# Summing.net
KiCad netlist of a schematic drawn in EAGLE
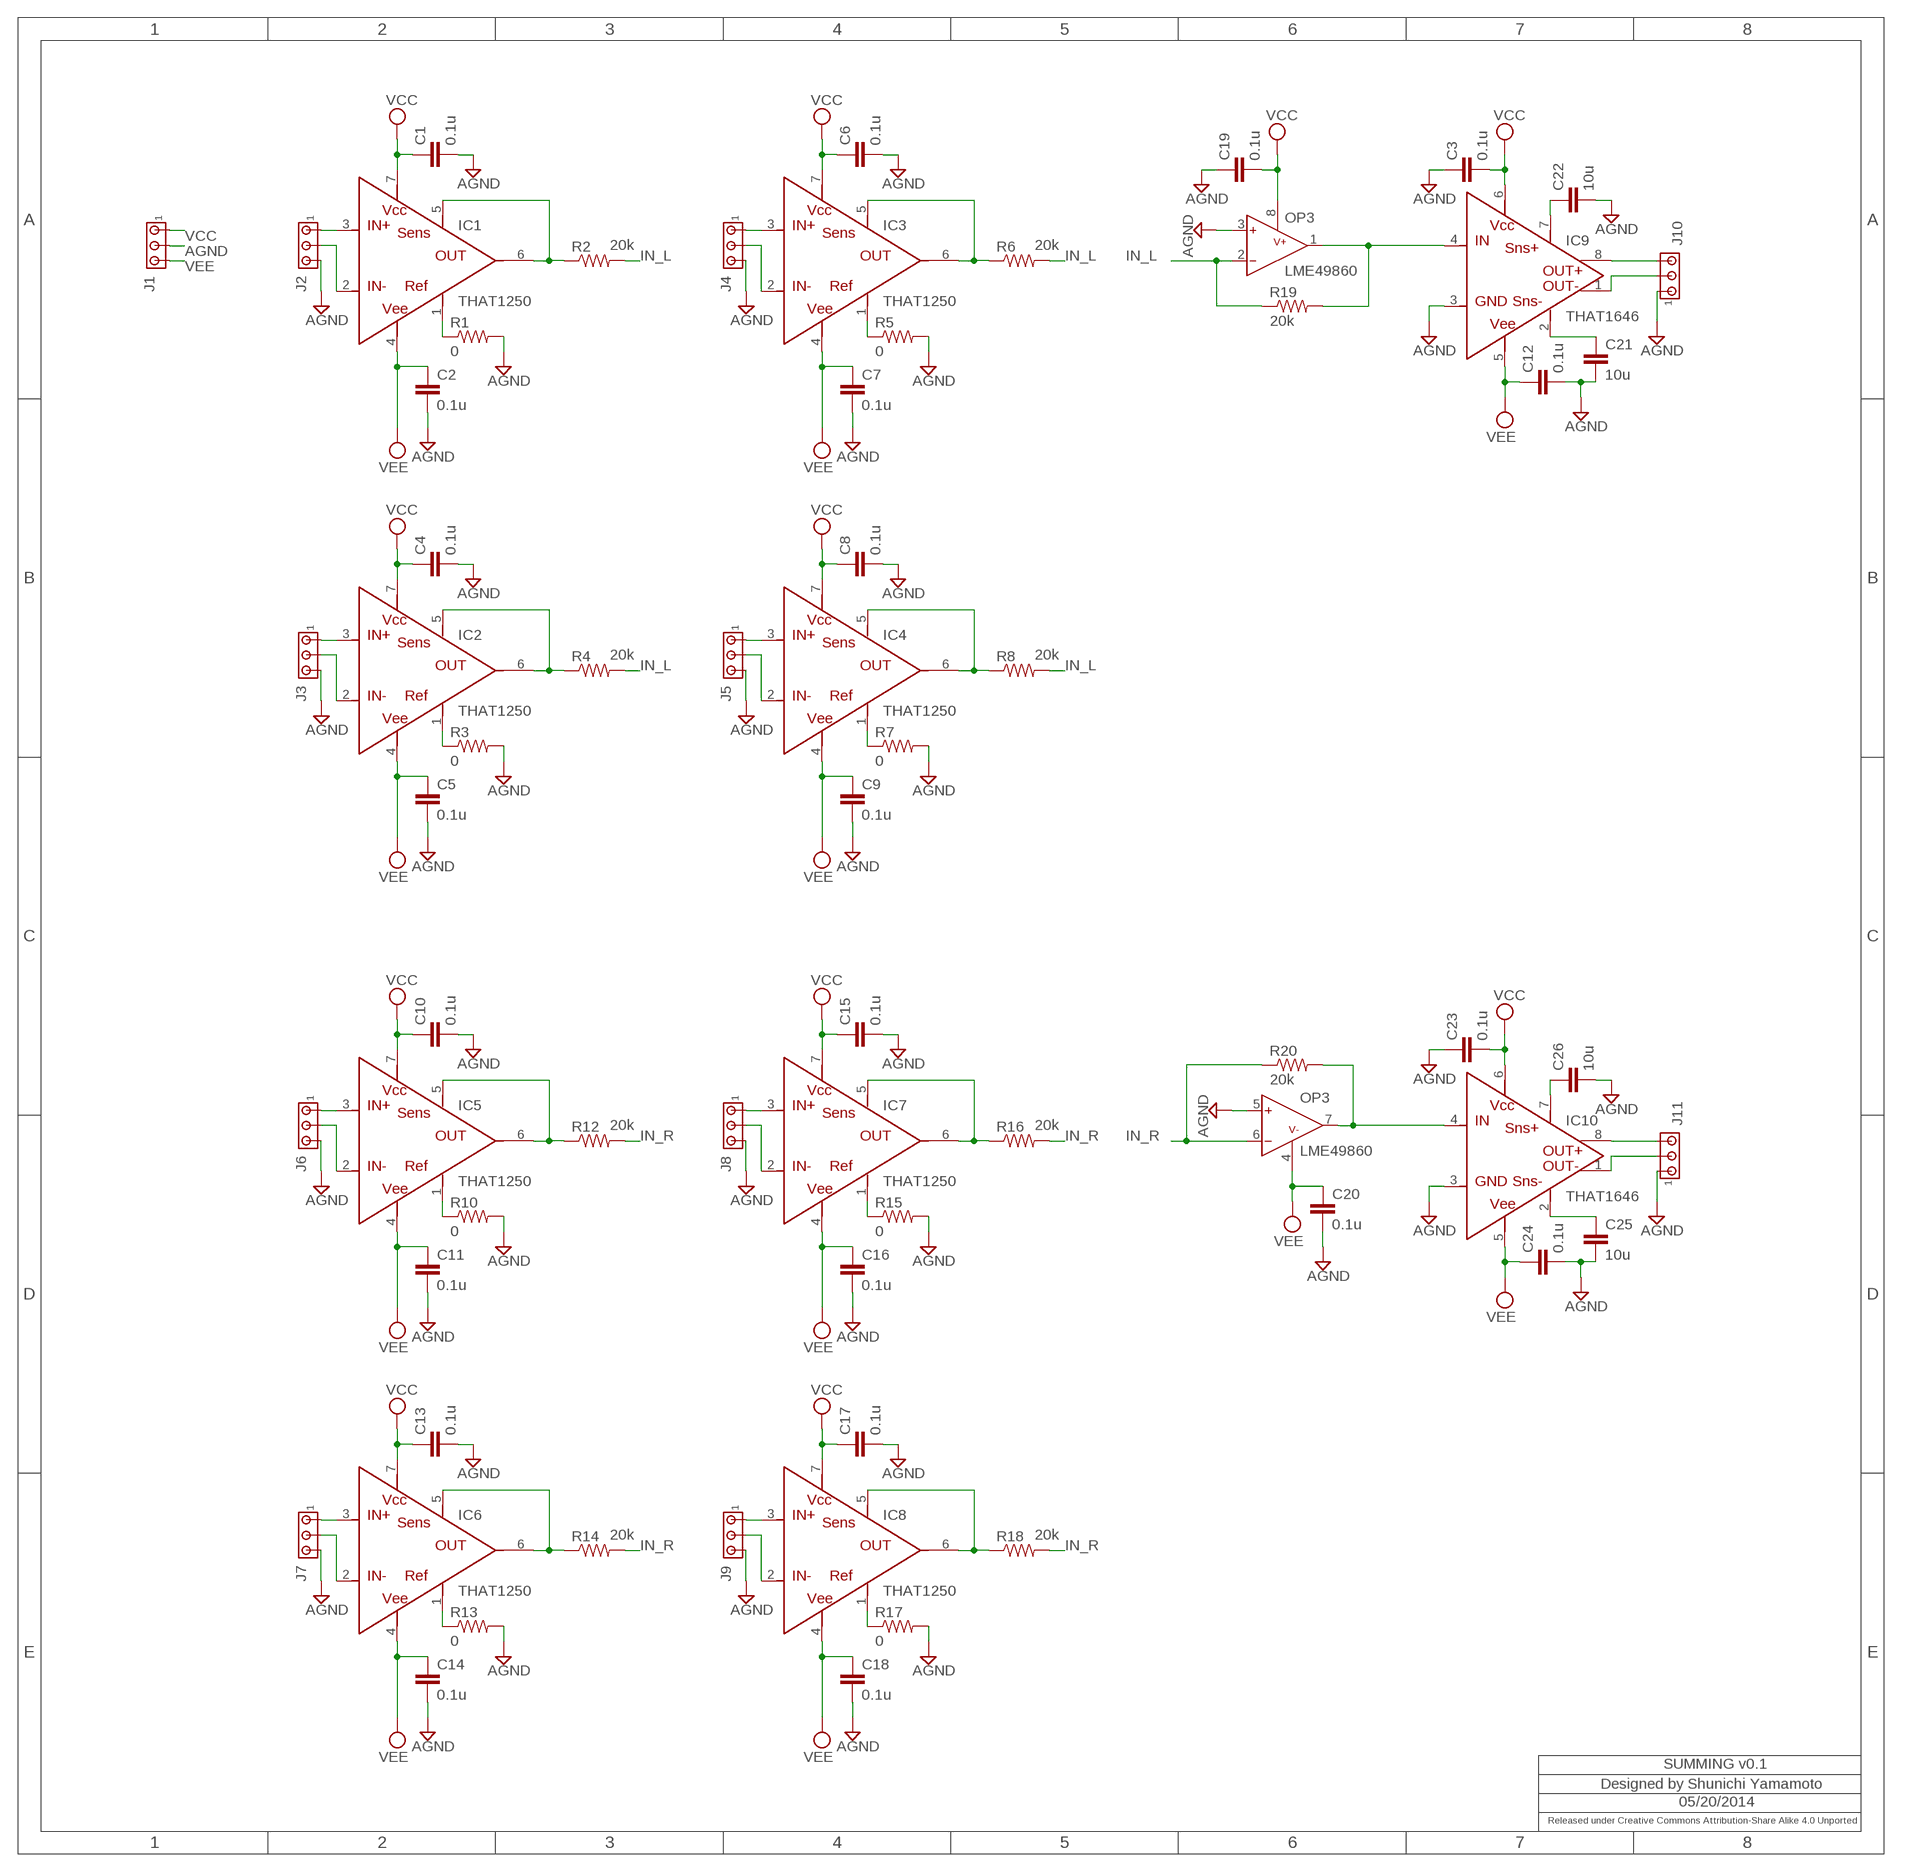
[diagram p0: schematic, sheet 1]

(export (version "E")
  (design (tool "Eeschema 10.0.6"))
  (components
    (comp (ref "C1")
      (value "0.1u")
      (footprint "eagle-import:C2012")
      (libsource (lib "eagle-import") (part "C-EUC2012"))
    )
    (comp (ref "C2")
      (value "0.1u")
      (footprint "eagle-import:C2012")
      (libsource (lib "eagle-import") (part "C-EUC2012"))
    )
    (comp (ref "C3")
      (value "0.1u")
      (footprint "eagle-import:C2012")
      (libsource (lib "eagle-import") (part "C-EUC2012"))
    )
    (comp (ref "C4")
      (value "0.1u")
      (footprint "eagle-import:C2012")
      (libsource (lib "eagle-import") (part "C-EUC2012"))
    )
    (comp (ref "C5")
      (value "0.1u")
      (footprint "eagle-import:C2012")
      (libsource (lib "eagle-import") (part "C-EUC2012"))
    )
    (comp (ref "C6")
      (value "0.1u")
      (footprint "eagle-import:C2012")
      (libsource (lib "eagle-import") (part "C-EUC2012"))
    )
    (comp (ref "C7")
      (value "0.1u")
      (footprint "eagle-import:C2012")
      (libsource (lib "eagle-import") (part "C-EUC2012"))
    )
    (comp (ref "C8")
      (value "0.1u")
      (footprint "eagle-import:C2012")
      (libsource (lib "eagle-import") (part "C-EUC2012"))
    )
    (comp (ref "C9")
      (value "0.1u")
      (footprint "eagle-import:C2012")
      (libsource (lib "eagle-import") (part "C-EUC2012"))
    )
    (comp (ref "C10")
      (value "0.1u")
      (footprint "eagle-import:C2012")
      (libsource (lib "eagle-import") (part "C-EUC2012"))
    )
    (comp (ref "C11")
      (value "0.1u")
      (footprint "eagle-import:C2012")
      (libsource (lib "eagle-import") (part "C-EUC2012"))
    )
    (comp (ref "C12")
      (value "0.1u")
      (footprint "eagle-import:C2012")
      (libsource (lib "eagle-import") (part "C-EUC2012"))
    )
    (comp (ref "C13")
      (value "0.1u")
      (footprint "eagle-import:C2012")
      (libsource (lib "eagle-import") (part "C-EUC2012"))
    )
    (comp (ref "C14")
      (value "0.1u")
      (footprint "eagle-import:C2012")
      (libsource (lib "eagle-import") (part "C-EUC2012"))
    )
    (comp (ref "C15")
      (value "0.1u")
      (footprint "eagle-import:C2012")
      (libsource (lib "eagle-import") (part "C-EUC2012"))
    )
    (comp (ref "C16")
      (value "0.1u")
      (footprint "eagle-import:C2012")
      (libsource (lib "eagle-import") (part "C-EUC2012"))
    )
    (comp (ref "C17")
      (value "0.1u")
      (footprint "eagle-import:C2012")
      (libsource (lib "eagle-import") (part "C-EUC2012"))
    )
    (comp (ref "C18")
      (value "0.1u")
      (footprint "eagle-import:C2012")
      (libsource (lib "eagle-import") (part "C-EUC2012"))
    )
    (comp (ref "C19")
      (value "0.1u")
      (footprint "eagle-import:C2012")
      (libsource (lib "eagle-import") (part "C-EUC2012"))
    )
    (comp (ref "C20")
      (value "0.1u")
      (footprint "eagle-import:C2012")
      (libsource (lib "eagle-import") (part "C-EUC2012"))
    )
    (comp (ref "C21")
      (value "10u")
      (footprint "eagle-import:C2012")
      (libsource (lib "eagle-import") (part "C-EUC2012"))
    )
    (comp (ref "C22")
      (value "10u")
      (footprint "eagle-import:C2012")
      (libsource (lib "eagle-import") (part "C-EUC2012"))
    )
    (comp (ref "C23")
      (value "0.1u")
      (footprint "eagle-import:C2012")
      (libsource (lib "eagle-import") (part "C-EUC2012"))
    )
    (comp (ref "C24")
      (value "0.1u")
      (footprint "eagle-import:C2012")
      (libsource (lib "eagle-import") (part "C-EUC2012"))
    )
    (comp (ref "C25")
      (value "10u")
      (footprint "eagle-import:C2012")
      (libsource (lib "eagle-import") (part "C-EUC2012"))
    )
    (comp (ref "C26")
      (value "10u")
      (footprint "eagle-import:C2012")
      (libsource (lib "eagle-import") (part "C-EUC2012"))
    )
    (comp (ref "IC1")
      (value "THAT1250")
      (footprint "eagle-import:SOIC8@1")
      (libsource (lib "eagle-import") (part "THAT1250"))
    )
    (comp (ref "IC2")
      (value "THAT1250")
      (footprint "eagle-import:SOIC8@1")
      (libsource (lib "eagle-import") (part "THAT1250"))
    )
    (comp (ref "IC3")
      (value "THAT1250")
      (footprint "eagle-import:SOIC8@1")
      (libsource (lib "eagle-import") (part "THAT1250"))
    )
    (comp (ref "IC4")
      (value "THAT1250")
      (footprint "eagle-import:SOIC8@1")
      (libsource (lib "eagle-import") (part "THAT1250"))
    )
    (comp (ref "IC5")
      (value "THAT1250")
      (footprint "eagle-import:SOIC8@1")
      (libsource (lib "eagle-import") (part "THAT1250"))
    )
    (comp (ref "IC6")
      (value "THAT1250")
      (footprint "eagle-import:SOIC8@1")
      (libsource (lib "eagle-import") (part "THAT1250"))
    )
    (comp (ref "IC7")
      (value "THAT1250")
      (footprint "eagle-import:SOIC8@1")
      (libsource (lib "eagle-import") (part "THAT1250"))
    )
    (comp (ref "IC8")
      (value "THAT1250")
      (footprint "eagle-import:SOIC8@1")
      (libsource (lib "eagle-import") (part "THAT1250"))
    )
    (comp (ref "IC9")
      (value "THAT1646")
      (footprint "eagle-import:SOIC8")
      (libsource (lib "eagle-import") (part "THAT1646"))
    )
    (comp (ref "IC10")
      (value "THAT1646")
      (footprint "eagle-import:SOIC8")
      (libsource (lib "eagle-import") (part "THAT1646"))
    )
    (comp (ref "J1")
      (value "MTA03-156")
      (footprint "eagle-import:1X3MTA")
      (libsource (lib "eagle-import") (part "MTA03-156"))
    )
    (comp (ref "J2")
      (value "MTA03-100")
      (footprint "eagle-import:10X03MTA")
      (libsource (lib "eagle-import") (part "MTA03-100"))
    )
    (comp (ref "J3")
      (value "MTA03-100")
      (footprint "eagle-import:10X03MTA")
      (libsource (lib "eagle-import") (part "MTA03-100"))
    )
    (comp (ref "J4")
      (value "MTA03-100")
      (footprint "eagle-import:10X03MTA")
      (libsource (lib "eagle-import") (part "MTA03-100"))
    )
    (comp (ref "J5")
      (value "MTA03-100")
      (footprint "eagle-import:10X03MTA")
      (libsource (lib "eagle-import") (part "MTA03-100"))
    )
    (comp (ref "J6")
      (value "MTA03-100")
      (footprint "eagle-import:10X03MTA")
      (libsource (lib "eagle-import") (part "MTA03-100"))
    )
    (comp (ref "J7")
      (value "MTA03-100")
      (footprint "eagle-import:10X03MTA")
      (libsource (lib "eagle-import") (part "MTA03-100"))
    )
    (comp (ref "J8")
      (value "MTA03-100")
      (footprint "eagle-import:10X03MTA")
      (libsource (lib "eagle-import") (part "MTA03-100"))
    )
    (comp (ref "J9")
      (value "MTA03-100")
      (footprint "eagle-import:10X03MTA")
      (libsource (lib "eagle-import") (part "MTA03-100"))
    )
    (comp (ref "J10")
      (value "MTA03-100")
      (footprint "eagle-import:10X03MTA")
      (libsource (lib "eagle-import") (part "MTA03-100"))
    )
    (comp (ref "J11")
      (value "MTA03-100")
      (footprint "eagle-import:10X03MTA")
      (libsource (lib "eagle-import") (part "MTA03-100"))
    )
    (comp (ref "OP3")
      (value "LME49860")
      (footprint "eagle-import:SOIC8@2")
      (libsource (lib "eagle-import") (part "LME49860"))
    )
    (comp (ref "R1")
      (value "0")
      (footprint "eagle-import:0805")
      (libsource (lib "eagle-import") (part "RESISTOR0805-RES"))
    )
    (comp (ref "R2")
      (value "20k")
      (footprint "eagle-import:0805")
      (libsource (lib "eagle-import") (part "RESISTOR0805-RES"))
    )
    (comp (ref "R3")
      (value "0")
      (footprint "eagle-import:0805")
      (libsource (lib "eagle-import") (part "RESISTOR0805-RES"))
    )
    (comp (ref "R4")
      (value "20k")
      (footprint "eagle-import:0805")
      (libsource (lib "eagle-import") (part "RESISTOR0805-RES"))
    )
    (comp (ref "R5")
      (value "0")
      (footprint "eagle-import:0805")
      (libsource (lib "eagle-import") (part "RESISTOR0805-RES"))
    )
    (comp (ref "R6")
      (value "20k")
      (footprint "eagle-import:0805")
      (libsource (lib "eagle-import") (part "RESISTOR0805-RES"))
    )
    (comp (ref "R7")
      (value "0")
      (footprint "eagle-import:0805")
      (libsource (lib "eagle-import") (part "RESISTOR0805-RES"))
    )
    (comp (ref "R8")
      (value "20k")
      (footprint "eagle-import:0805")
      (libsource (lib "eagle-import") (part "RESISTOR0805-RES"))
    )
    (comp (ref "R10")
      (value "0")
      (footprint "eagle-import:0805")
      (libsource (lib "eagle-import") (part "RESISTOR0805-RES"))
    )
    (comp (ref "R12")
      (value "20k")
      (footprint "eagle-import:0805")
      (libsource (lib "eagle-import") (part "RESISTOR0805-RES"))
    )
    (comp (ref "R13")
      (value "0")
      (footprint "eagle-import:0805")
      (libsource (lib "eagle-import") (part "RESISTOR0805-RES"))
    )
    (comp (ref "R14")
      (value "20k")
      (footprint "eagle-import:0805")
      (libsource (lib "eagle-import") (part "RESISTOR0805-RES"))
    )
    (comp (ref "R15")
      (value "0")
      (footprint "eagle-import:0805")
      (libsource (lib "eagle-import") (part "RESISTOR0805-RES"))
    )
    (comp (ref "R16")
      (value "20k")
      (footprint "eagle-import:0805")
      (libsource (lib "eagle-import") (part "RESISTOR0805-RES"))
    )
    (comp (ref "R17")
      (value "0")
      (footprint "eagle-import:0805")
      (libsource (lib "eagle-import") (part "RESISTOR0805-RES"))
    )
    (comp (ref "R18")
      (value "20k")
      (footprint "eagle-import:0805")
      (libsource (lib "eagle-import") (part "RESISTOR0805-RES"))
    )
    (comp (ref "R19")
      (value "20k")
      (footprint "eagle-import:0805")
      (libsource (lib "eagle-import") (part "RESISTOR0805-RES"))
    )
    (comp (ref "R20")
      (value "20k")
      (footprint "eagle-import:0805")
      (libsource (lib "eagle-import") (part "RESISTOR0805-RES"))
    )
  )
  (nets
    (net (code "1") (name "/IN_L") (class "Default")
      (node (ref "OP3") (pin "2") (pinfunction "INA-_2") (pintype "input"))
      (node (ref "R19") (pin "1") (pinfunction "1_1") (pintype "passive"))
      (node (ref "R2") (pin "2") (pinfunction "2_2") (pintype "passive"))
      (node (ref "R4") (pin "2") (pinfunction "2_2") (pintype "passive"))
      (node (ref "R6") (pin "2") (pinfunction "2_2") (pintype "passive"))
      (node (ref "R8") (pin "2") (pinfunction "2_2") (pintype "passive"))
    )
    (net (code "2") (name "/IN_R") (class "Default")
      (node (ref "OP3") (pin "6") (pinfunction "INB-_6") (pintype "input"))
      (node (ref "R12") (pin "2") (pinfunction "2_2") (pintype "passive"))
      (node (ref "R14") (pin "2") (pinfunction "2_2") (pintype "passive"))
      (node (ref "R16") (pin "2") (pinfunction "2_2") (pintype "passive"))
      (node (ref "R18") (pin "2") (pinfunction "2_2") (pintype "passive"))
      (node (ref "R20") (pin "1") (pinfunction "1_1") (pintype "passive"))
    )
    (net (code "3") (name "AGND") (class "Default")
      (node (ref "C1") (pin "2") (pinfunction "2_2") (pintype "passive"))
      (node (ref "C10") (pin "2") (pinfunction "2_2") (pintype "passive"))
      (node (ref "C11") (pin "2") (pinfunction "2_2") (pintype "passive"))
      (node (ref "C12") (pin "2") (pinfunction "2_2") (pintype "passive"))
      (node (ref "C13") (pin "2") (pinfunction "2_2") (pintype "passive"))
      (node (ref "C14") (pin "2") (pinfunction "2_2") (pintype "passive"))
      (node (ref "C15") (pin "2") (pinfunction "2_2") (pintype "passive"))
      (node (ref "C16") (pin "2") (pinfunction "2_2") (pintype "passive"))
      (node (ref "C17") (pin "2") (pinfunction "2_2") (pintype "passive"))
      (node (ref "C18") (pin "2") (pinfunction "2_2") (pintype "passive"))
      (node (ref "C19") (pin "1") (pinfunction "1_1") (pintype "passive"))
      (node (ref "C2") (pin "2") (pinfunction "2_2") (pintype "passive"))
      (node (ref "C20") (pin "2") (pinfunction "2_2") (pintype "passive"))
      (node (ref "C21") (pin "2") (pinfunction "2_2") (pintype "passive"))
      (node (ref "C22") (pin "2") (pinfunction "2_2") (pintype "passive"))
      (node (ref "C23") (pin "1") (pinfunction "1_1") (pintype "passive"))
      (node (ref "C24") (pin "2") (pinfunction "2_2") (pintype "passive"))
      (node (ref "C25") (pin "2") (pinfunction "2_2") (pintype "passive"))
      (node (ref "C26") (pin "2") (pinfunction "2_2") (pintype "passive"))
      (node (ref "C3") (pin "1") (pinfunction "1_1") (pintype "passive"))
      (node (ref "C4") (pin "2") (pinfunction "2_2") (pintype "passive"))
      (node (ref "C5") (pin "2") (pinfunction "2_2") (pintype "passive"))
      (node (ref "C6") (pin "2") (pinfunction "2_2") (pintype "passive"))
      (node (ref "C7") (pin "2") (pinfunction "2_2") (pintype "passive"))
      (node (ref "C8") (pin "2") (pinfunction "2_2") (pintype "passive"))
      (node (ref "C9") (pin "2") (pinfunction "2_2") (pintype "passive"))
      (node (ref "IC10") (pin "3") (pinfunction "GND_3") (pintype "input"))
      (node (ref "IC9") (pin "3") (pinfunction "GND_3") (pintype "input"))
      (node (ref "J1") (pin "2") (pinfunction "2_2") (pintype "passive"))
      (node (ref "J10") (pin "1") (pinfunction "1_1") (pintype "passive"))
      (node (ref "J11") (pin "1") (pinfunction "1_1") (pintype "passive"))
      (node (ref "J2") (pin "3") (pinfunction "3_3") (pintype "passive"))
      (node (ref "J3") (pin "3") (pinfunction "3_3") (pintype "passive"))
      (node (ref "J4") (pin "3") (pinfunction "3_3") (pintype "passive"))
      (node (ref "J5") (pin "3") (pinfunction "3_3") (pintype "passive"))
      (node (ref "J6") (pin "3") (pinfunction "3_3") (pintype "passive"))
      (node (ref "J7") (pin "3") (pinfunction "3_3") (pintype "passive"))
      (node (ref "J8") (pin "3") (pinfunction "3_3") (pintype "passive"))
      (node (ref "J9") (pin "3") (pinfunction "3_3") (pintype "passive"))
      (node (ref "OP3") (pin "3") (pinfunction "INA+_3") (pintype "input"))
      (node (ref "OP3") (pin "5") (pinfunction "INB+_5") (pintype "input"))
      (node (ref "R1") (pin "2") (pinfunction "2_2") (pintype "passive"))
      (node (ref "R10") (pin "2") (pinfunction "2_2") (pintype "passive"))
      (node (ref "R13") (pin "2") (pinfunction "2_2") (pintype "passive"))
      (node (ref "R15") (pin "2") (pinfunction "2_2") (pintype "passive"))
      (node (ref "R17") (pin "2") (pinfunction "2_2") (pintype "passive"))
      (node (ref "R3") (pin "2") (pinfunction "2_2") (pintype "passive"))
      (node (ref "R5") (pin "2") (pinfunction "2_2") (pintype "passive"))
      (node (ref "R7") (pin "2") (pinfunction "2_2") (pintype "passive"))
    )
    (net (code "4") (name "Net-(IC1-IN+)") (class "Default")
      (node (ref "IC1") (pin "3") (pinfunction "IN+_3") (pintype "input"))
      (node (ref "J2") (pin "1") (pinfunction "1_1") (pintype "passive"))
    )
    (net (code "5") (name "Net-(IC1-IN-)") (class "Default")
      (node (ref "IC1") (pin "2") (pinfunction "IN-_2") (pintype "input"))
      (node (ref "J2") (pin "2") (pinfunction "2_2") (pintype "passive"))
    )
    (net (code "6") (name "Net-(IC1-OUT)") (class "Default")
      (node (ref "IC1") (pin "5") (pinfunction "SENS_5") (pintype "power_in"))
      (node (ref "IC1") (pin "6") (pinfunction "OUT_6") (pintype "output"))
      (node (ref "R2") (pin "1") (pinfunction "1_1") (pintype "passive"))
    )
    (net (code "7") (name "Net-(IC1-REF)") (class "Default")
      (node (ref "IC1") (pin "1") (pinfunction "REF_1") (pintype "input"))
      (node (ref "R1") (pin "1") (pinfunction "1_1") (pintype "passive"))
    )
    (net (code "8") (name "Net-(IC2-IN+)") (class "Default")
      (node (ref "IC2") (pin "3") (pinfunction "IN+_3") (pintype "input"))
      (node (ref "J3") (pin "1") (pinfunction "1_1") (pintype "passive"))
    )
    (net (code "9") (name "Net-(IC2-IN-)") (class "Default")
      (node (ref "IC2") (pin "2") (pinfunction "IN-_2") (pintype "input"))
      (node (ref "J3") (pin "2") (pinfunction "2_2") (pintype "passive"))
    )
    (net (code "10") (name "Net-(IC2-OUT)") (class "Default")
      (node (ref "IC2") (pin "5") (pinfunction "SENS_5") (pintype "power_in"))
      (node (ref "IC2") (pin "6") (pinfunction "OUT_6") (pintype "output"))
      (node (ref "R4") (pin "1") (pinfunction "1_1") (pintype "passive"))
    )
    (net (code "11") (name "Net-(IC2-REF)") (class "Default")
      (node (ref "IC2") (pin "1") (pinfunction "REF_1") (pintype "input"))
      (node (ref "R3") (pin "1") (pinfunction "1_1") (pintype "passive"))
    )
    (net (code "12") (name "Net-(IC3-IN+)") (class "Default")
      (node (ref "IC3") (pin "3") (pinfunction "IN+_3") (pintype "input"))
      (node (ref "J4") (pin "1") (pinfunction "1_1") (pintype "passive"))
    )
    (net (code "13") (name "Net-(IC3-IN-)") (class "Default")
      (node (ref "IC3") (pin "2") (pinfunction "IN-_2") (pintype "input"))
      (node (ref "J4") (pin "2") (pinfunction "2_2") (pintype "passive"))
    )
    (net (code "14") (name "Net-(IC3-OUT)") (class "Default")
      (node (ref "IC3") (pin "5") (pinfunction "SENS_5") (pintype "power_in"))
      (node (ref "IC3") (pin "6") (pinfunction "OUT_6") (pintype "output"))
      (node (ref "R6") (pin "1") (pinfunction "1_1") (pintype "passive"))
    )
    (net (code "15") (name "Net-(IC3-REF)") (class "Default")
      (node (ref "IC3") (pin "1") (pinfunction "REF_1") (pintype "input"))
      (node (ref "R5") (pin "1") (pinfunction "1_1") (pintype "passive"))
    )
    (net (code "16") (name "Net-(IC4-IN+)") (class "Default")
      (node (ref "IC4") (pin "3") (pinfunction "IN+_3") (pintype "input"))
      (node (ref "J5") (pin "1") (pinfunction "1_1") (pintype "passive"))
    )
    (net (code "17") (name "Net-(IC4-IN-)") (class "Default")
      (node (ref "IC4") (pin "2") (pinfunction "IN-_2") (pintype "input"))
      (node (ref "J5") (pin "2") (pinfunction "2_2") (pintype "passive"))
    )
    (net (code "18") (name "Net-(IC4-OUT)") (class "Default")
      (node (ref "IC4") (pin "5") (pinfunction "SENS_5") (pintype "power_in"))
      (node (ref "IC4") (pin "6") (pinfunction "OUT_6") (pintype "output"))
      (node (ref "R8") (pin "1") (pinfunction "1_1") (pintype "passive"))
    )
    (net (code "19") (name "Net-(IC4-REF)") (class "Default")
      (node (ref "IC4") (pin "1") (pinfunction "REF_1") (pintype "input"))
      (node (ref "R7") (pin "1") (pinfunction "1_1") (pintype "passive"))
    )
    (net (code "20") (name "Net-(IC5-IN+)") (class "Default")
      (node (ref "IC5") (pin "3") (pinfunction "IN+_3") (pintype "input"))
      (node (ref "J6") (pin "1") (pinfunction "1_1") (pintype "passive"))
    )
    (net (code "21") (name "Net-(IC5-IN-)") (class "Default")
      (node (ref "IC5") (pin "2") (pinfunction "IN-_2") (pintype "input"))
      (node (ref "J6") (pin "2") (pinfunction "2_2") (pintype "passive"))
    )
    (net (code "22") (name "Net-(IC5-OUT)") (class "Default")
      (node (ref "IC5") (pin "5") (pinfunction "SENS_5") (pintype "power_in"))
      (node (ref "IC5") (pin "6") (pinfunction "OUT_6") (pintype "output"))
      (node (ref "R12") (pin "1") (pinfunction "1_1") (pintype "passive"))
    )
    (net (code "23") (name "Net-(IC5-REF)") (class "Default")
      (node (ref "IC5") (pin "1") (pinfunction "REF_1") (pintype "input"))
      (node (ref "R10") (pin "1") (pinfunction "1_1") (pintype "passive"))
    )
    (net (code "24") (name "Net-(IC6-IN+)") (class "Default")
      (node (ref "IC6") (pin "3") (pinfunction "IN+_3") (pintype "input"))
      (node (ref "J7") (pin "1") (pinfunction "1_1") (pintype "passive"))
    )
    (net (code "25") (name "Net-(IC6-IN-)") (class "Default")
      (node (ref "IC6") (pin "2") (pinfunction "IN-_2") (pintype "input"))
      (node (ref "J7") (pin "2") (pinfunction "2_2") (pintype "passive"))
    )
    (net (code "26") (name "Net-(IC6-OUT)") (class "Default")
      (node (ref "IC6") (pin "5") (pinfunction "SENS_5") (pintype "power_in"))
      (node (ref "IC6") (pin "6") (pinfunction "OUT_6") (pintype "output"))
      (node (ref "R14") (pin "1") (pinfunction "1_1") (pintype "passive"))
    )
    (net (code "27") (name "Net-(IC6-REF)") (class "Default")
      (node (ref "IC6") (pin "1") (pinfunction "REF_1") (pintype "input"))
      (node (ref "R13") (pin "1") (pinfunction "1_1") (pintype "passive"))
    )
    (net (code "28") (name "Net-(IC7-IN+)") (class "Default")
      (node (ref "IC7") (pin "3") (pinfunction "IN+_3") (pintype "input"))
      (node (ref "J8") (pin "1") (pinfunction "1_1") (pintype "passive"))
    )
    (net (code "29") (name "Net-(IC7-IN-)") (class "Default")
      (node (ref "IC7") (pin "2") (pinfunction "IN-_2") (pintype "input"))
      (node (ref "J8") (pin "2") (pinfunction "2_2") (pintype "passive"))
    )
    (net (code "30") (name "Net-(IC7-OUT)") (class "Default")
      (node (ref "IC7") (pin "5") (pinfunction "SENS_5") (pintype "power_in"))
      (node (ref "IC7") (pin "6") (pinfunction "OUT_6") (pintype "output"))
      (node (ref "R16") (pin "1") (pinfunction "1_1") (pintype "passive"))
    )
    (net (code "31") (name "Net-(IC7-REF)") (class "Default")
      (node (ref "IC7") (pin "1") (pinfunction "REF_1") (pintype "input"))
      (node (ref "R15") (pin "1") (pinfunction "1_1") (pintype "passive"))
    )
    (net (code "32") (name "Net-(IC8-IN+)") (class "Default")
      (node (ref "IC8") (pin "3") (pinfunction "IN+_3") (pintype "input"))
      (node (ref "J9") (pin "1") (pinfunction "1_1") (pintype "passive"))
    )
    (net (code "33") (name "Net-(IC8-IN-)") (class "Default")
      (node (ref "IC8") (pin "2") (pinfunction "IN-_2") (pintype "input"))
      (node (ref "J9") (pin "2") (pinfunction "2_2") (pintype "passive"))
    )
    (net (code "34") (name "Net-(IC8-OUT)") (class "Default")
      (node (ref "IC8") (pin "5") (pinfunction "SENS_5") (pintype "power_in"))
      (node (ref "IC8") (pin "6") (pinfunction "OUT_6") (pintype "output"))
      (node (ref "R18") (pin "1") (pinfunction "1_1") (pintype "passive"))
    )
    (net (code "35") (name "Net-(IC8-REF)") (class "Default")
      (node (ref "IC8") (pin "1") (pinfunction "REF_1") (pintype "input"))
      (node (ref "R17") (pin "1") (pinfunction "1_1") (pintype "passive"))
    )
    (net (code "36") (name "Net-(IC9-IN)") (class "Default")
      (node (ref "IC9") (pin "4") (pinfunction "IN_4") (pintype "input"))
      (node (ref "OP3") (pin "1") (pinfunction "OUTA_1") (pintype "output"))
      (node (ref "R19") (pin "2") (pinfunction "2_2") (pintype "passive"))
    )
    (net (code "37") (name "Net-(IC9-OUT+)") (class "Default")
      (node (ref "IC9") (pin "8") (pinfunction "OUT+_8") (pintype "output"))
      (node (ref "J10") (pin "3") (pinfunction "3_3") (pintype "passive"))
    )
    (net (code "38") (name "Net-(IC9-OUT-)") (class "Default")
      (node (ref "IC9") (pin "1") (pinfunction "OUT-_1") (pintype "output"))
      (node (ref "J10") (pin "2") (pinfunction "2_2") (pintype "passive"))
    )
    (net (code "39") (name "Net-(IC9-SNS+)") (class "Default")
      (node (ref "C22") (pin "1") (pinfunction "1_1") (pintype "passive"))
      (node (ref "IC9") (pin "7") (pinfunction "SNS+_7") (pintype "power_in"))
    )
    (net (code "40") (name "Net-(IC9-SNS-)") (class "Default")
      (node (ref "C21") (pin "1") (pinfunction "1_1") (pintype "passive"))
      (node (ref "IC9") (pin "2") (pinfunction "SNS-_2") (pintype "input"))
    )
    (net (code "41") (name "Net-(IC10-IN)") (class "Default")
      (node (ref "IC10") (pin "4") (pinfunction "IN_4") (pintype "input"))
      (node (ref "OP3") (pin "7") (pinfunction "OUTB_7") (pintype "output"))
      (node (ref "R20") (pin "2") (pinfunction "2_2") (pintype "passive"))
    )
    (net (code "42") (name "Net-(IC10-OUT+)") (class "Default")
      (node (ref "IC10") (pin "8") (pinfunction "OUT+_8") (pintype "output"))
      (node (ref "J11") (pin "3") (pinfunction "3_3") (pintype "passive"))
    )
    (net (code "43") (name "Net-(IC10-OUT-)") (class "Default")
      (node (ref "IC10") (pin "1") (pinfunction "OUT-_1") (pintype "output"))
      (node (ref "J11") (pin "2") (pinfunction "2_2") (pintype "passive"))
    )
    (net (code "44") (name "Net-(IC10-SNS+)") (class "Default")
      (node (ref "C26") (pin "1") (pinfunction "1_1") (pintype "passive"))
      (node (ref "IC10") (pin "7") (pinfunction "SNS+_7") (pintype "power_in"))
    )
    (net (code "45") (name "Net-(IC10-SNS-)") (class "Default")
      (node (ref "C25") (pin "1") (pinfunction "1_1") (pintype "passive"))
      (node (ref "IC10") (pin "2") (pinfunction "SNS-_2") (pintype "input"))
    )
    (net (code "46") (name "VCC") (class "Default")
      (node (ref "C1") (pin "1") (pinfunction "1_1") (pintype "passive"))
      (node (ref "C10") (pin "1") (pinfunction "1_1") (pintype "passive"))
      (node (ref "C13") (pin "1") (pinfunction "1_1") (pintype "passive"))
      (node (ref "C15") (pin "1") (pinfunction "1_1") (pintype "passive"))
      (node (ref "C17") (pin "1") (pinfunction "1_1") (pintype "passive"))
      (node (ref "C19") (pin "2") (pinfunction "2_2") (pintype "passive"))
      (node (ref "C23") (pin "2") (pinfunction "2_2") (pintype "passive"))
      (node (ref "C3") (pin "2") (pinfunction "2_2") (pintype "passive"))
      (node (ref "C4") (pin "1") (pinfunction "1_1") (pintype "passive"))
      (node (ref "C6") (pin "1") (pinfunction "1_1") (pintype "passive"))
      (node (ref "C8") (pin "1") (pinfunction "1_1") (pintype "passive"))
      (node (ref "IC1") (pin "7") (pinfunction "VCC_7") (pintype "power_in"))
      (node (ref "IC10") (pin "6") (pinfunction "VCC_6") (pintype "bidirectional"))
      (node (ref "IC2") (pin "7") (pinfunction "VCC_7") (pintype "power_in"))
      (node (ref "IC3") (pin "7") (pinfunction "VCC_7") (pintype "power_in"))
      (node (ref "IC4") (pin "7") (pinfunction "VCC_7") (pintype "power_in"))
      (node (ref "IC5") (pin "7") (pinfunction "VCC_7") (pintype "power_in"))
      (node (ref "IC6") (pin "7") (pinfunction "VCC_7") (pintype "power_in"))
      (node (ref "IC7") (pin "7") (pinfunction "VCC_7") (pintype "power_in"))
      (node (ref "IC8") (pin "7") (pinfunction "VCC_7") (pintype "power_in"))
      (node (ref "IC9") (pin "6") (pinfunction "VCC_6") (pintype "bidirectional"))
      (node (ref "J1") (pin "1") (pinfunction "1_1") (pintype "passive"))
      (node (ref "OP3") (pin "8") (pinfunction "V+_8") (pintype "power_in"))
    )
    (net (code "47") (name "VEE") (class "Default")
      (node (ref "C11") (pin "1") (pinfunction "1_1") (pintype "passive"))
      (node (ref "C12") (pin "1") (pinfunction "1_1") (pintype "passive"))
      (node (ref "C14") (pin "1") (pinfunction "1_1") (pintype "passive"))
      (node (ref "C16") (pin "1") (pinfunction "1_1") (pintype "passive"))
      (node (ref "C18") (pin "1") (pinfunction "1_1") (pintype "passive"))
      (node (ref "C2") (pin "1") (pinfunction "1_1") (pintype "passive"))
      (node (ref "C20") (pin "1") (pinfunction "1_1") (pintype "passive"))
      (node (ref "C24") (pin "1") (pinfunction "1_1") (pintype "passive"))
      (node (ref "C5") (pin "1") (pinfunction "1_1") (pintype "passive"))
      (node (ref "C7") (pin "1") (pinfunction "1_1") (pintype "passive"))
      (node (ref "C9") (pin "1") (pinfunction "1_1") (pintype "passive"))
      (node (ref "IC1") (pin "4") (pinfunction "VEE_4") (pintype "power_in"))
      (node (ref "IC10") (pin "5") (pinfunction "VEE_5") (pintype "input"))
      (node (ref "IC2") (pin "4") (pinfunction "VEE_4") (pintype "power_in"))
      (node (ref "IC3") (pin "4") (pinfunction "VEE_4") (pintype "power_in"))
      (node (ref "IC4") (pin "4") (pinfunction "VEE_4") (pintype "power_in"))
      (node (ref "IC5") (pin "4") (pinfunction "VEE_4") (pintype "power_in"))
      (node (ref "IC6") (pin "4") (pinfunction "VEE_4") (pintype "power_in"))
      (node (ref "IC7") (pin "4") (pinfunction "VEE_4") (pintype "power_in"))
      (node (ref "IC8") (pin "4") (pinfunction "VEE_4") (pintype "power_in"))
      (node (ref "IC9") (pin "5") (pinfunction "VEE_5") (pintype "input"))
      (node (ref "J1") (pin "3") (pinfunction "3_3") (pintype "passive"))
      (node (ref "OP3") (pin "4") (pinfunction "V-_4") (pintype "power_in"))
    )
  )
)
